# filter-1.net
KiCad netlist of a schematic drawn in Altium Designer
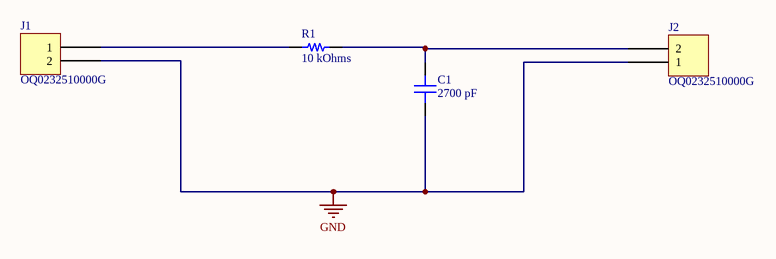
[diagram p0: filter-1.SchDoc]

(export (version "E")
  (design (tool "Eeschema 10.0.6"))
  (components
    (comp (ref "C1")
      (value "2700 pF")
      (footprint "CAP 0603_1608")
      (description "CAP CER 2700PF 25V NP0 0603")
      (fields (field (name "PART NUMBER") "C0603C272F3GAC7867") (field (name "MANUFACTURER") "KEMET"))
      (libsource (lib "Celestial Altium Library - altium_library") (part "Capacitor"))
    )
    (comp (ref "J1")
      (value "OQ0232510000G")
      (footprint "FCI 06-381-2PIN")
      (description "TERM BLOCK HDR 2POS 90DEG 3.81MM")
      (fields (field (name "MANUFACTURER") "Amphenol Anytek"))
      (libsource (lib "Celestial Altium Library - altium_library") (part "2 Pin"))
    )
    (comp (ref "J2")
      (value "OQ0232510000G")
      (footprint "FCI 06-381-2PIN")
      (description "TERM BLOCK HDR 2POS 90DEG 3.81MM")
      (fields (field (name "MANUFACTURER") "Amphenol Anytek"))
      (libsource (lib "") (part "2 Pin_1"))
    )
    (comp (ref "R1")
      (value "10 kOhms")
      (footprint "RES 0603_1608")
      (description "RES 10K OHM 0.1% 1/16W 0603")
      (fields
        (field (name "PART NUMBER") "RNCS0603BKE10K0")
        (field (name "MANUFACTURER") "Stackpole Electronics Inc")
      )
      (libsource (lib "Celestial Altium Library - altium_library") (part "Resistor"))
    )
  )
  (nets
    (net (code "1") (name "GND") (class "Default")
      (node (ref "C1") (pin "1") (pinfunction "1_1") (pintype "passive"))
      (node (ref "J1") (pin "2") (pinfunction "2_2") (pintype "passive"))
      (node (ref "J2") (pin "1") (pinfunction "1_1") (pintype "passive"))
    )
    (net (code "2") (name "Net-(C1-Pad2)") (class "Default")
      (node (ref "C1") (pin "2") (pinfunction "2_2") (pintype "passive"))
      (node (ref "J2") (pin "2") (pinfunction "2_2") (pintype "passive"))
      (node (ref "R1") (pin "2") (pinfunction "2_2") (pintype "passive"))
    )
    (net (code "3") (name "Net-(J1-Pad1)") (class "Default")
      (node (ref "J1") (pin "1") (pinfunction "1_1") (pintype "passive"))
      (node (ref "R1") (pin "1") (pinfunction "1_1") (pintype "passive"))
    )
  )
)
